# e-cig_controller.net
KiCad netlist of a schematic drawn in EAGLE
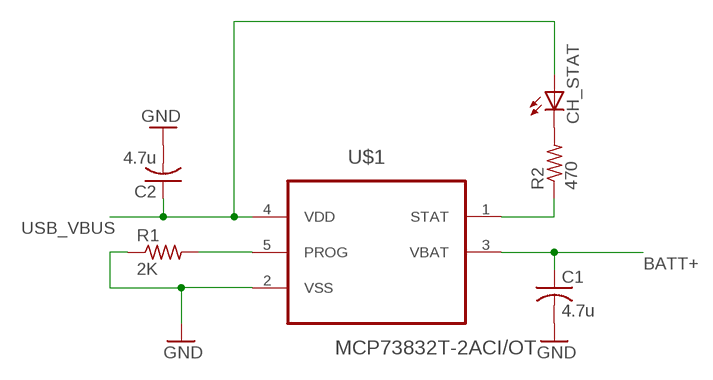
[diagram p0: schematic, sheet 1]
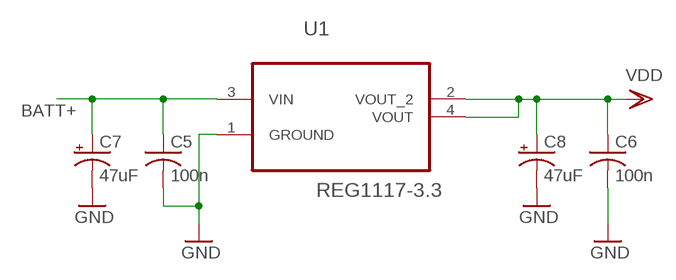
[diagram p1: schematic, sheet 2]
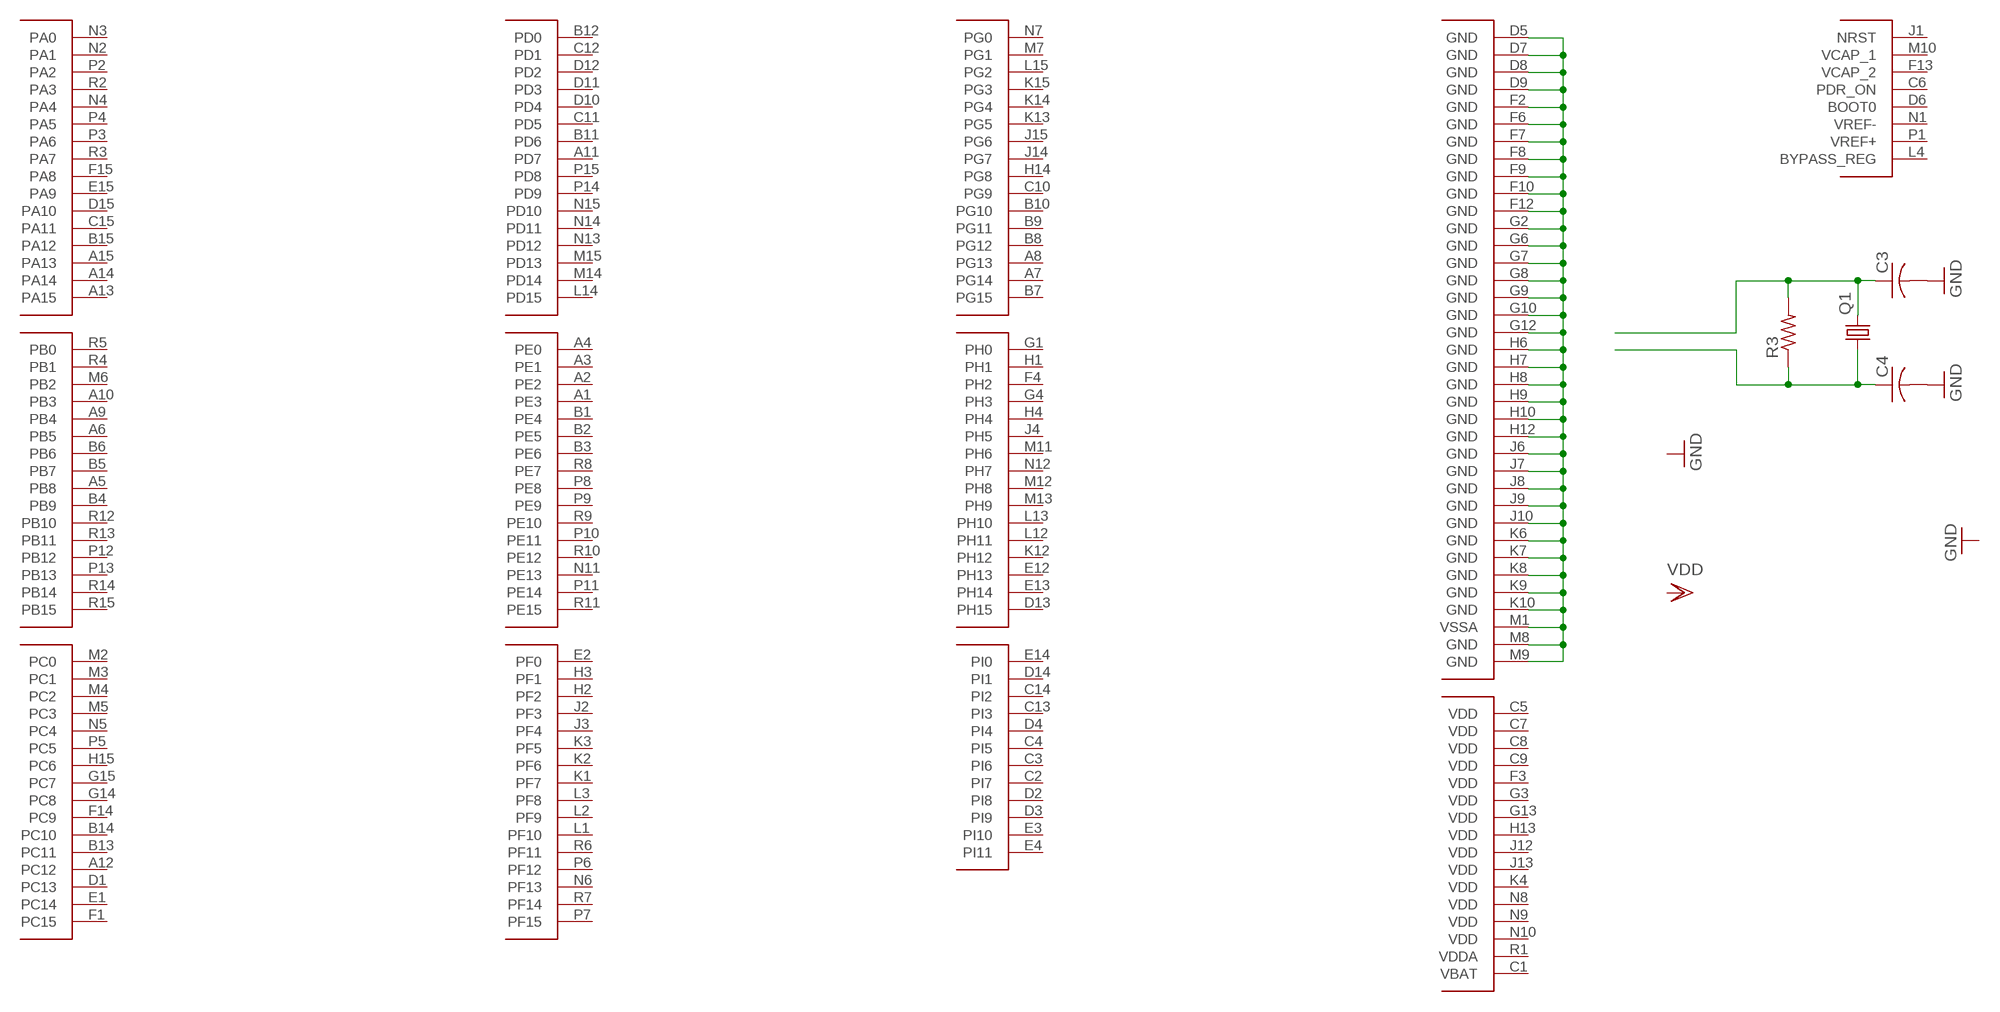
[diagram p2: schematic, sheet 3]

(export (version "E")
  (design (tool "Eeschema 10.0.6"))
  (components
    (comp (ref "C5")
      (value "100n")
      (footprint "eagle-import:C0603")
      (libsource (lib "eagle-import") (part "C-USC0603"))
    )
    (comp (ref "C6")
      (value "100n")
      (footprint "eagle-import:C0603")
      (libsource (lib "eagle-import") (part "C-USC0603"))
    )
    (comp (ref "C7")
      (value "47uF")
      (footprint "eagle-import:A_3216-18W")
      (libsource (lib "eagle-import") (part "CPOL-USA/3216-18W"))
    )
    (comp (ref "C8")
      (value "47uF")
      (footprint "eagle-import:A_3216-18W")
      (libsource (lib "eagle-import") (part "CPOL-USA/3216-18W"))
    )
    (comp (ref "U1")
      (value "REG1117-3.3")
      (footprint "eagle-import:SOT230P700X180-4N")
      (libsource (lib "eagle-import") (part "REG1117-3.3"))
    )
    (comp (ref "C1")
      (value "4.7u")
      (footprint "eagle-import:C0603")
      (libsource (lib "eagle-import") (part "C-USC0603"))
    )
    (comp (ref "C2")
      (value "4.7u")
      (footprint "eagle-import:C0603")
      (libsource (lib "eagle-import") (part "C-USC0603"))
    )
    (comp (ref "CH_STAT")
      (value "LEDCHIP-LED0603")
      (footprint "eagle-import:CHIP-LED0603")
      (libsource (lib "eagle-import") (part "LEDCHIP-LED0603"))
    )
    (comp (ref "R1")
      (value "2K")
      (footprint "eagle-import:R0603")
      (libsource (lib "eagle-import") (part "R-US_R0603"))
    )
    (comp (ref "R2")
      (value "470")
      (footprint "eagle-import:R0603")
      (libsource (lib "eagle-import") (part "R-US_R0603"))
    )
    (comp (ref "U$1")
      (value "MCP73832T-2ACI/OT")
      (footprint "eagle-import:SOT95P280X145-5N")
      (libsource (lib "eagle-import") (part "MCP73832T-2ACI/OT"))
    )
    (comp (ref "C3")
      (value "C-USC0603")
      (footprint "eagle-import:C0603")
      (libsource (lib "eagle-import") (part "C-USC0603"))
    )
    (comp (ref "C4")
      (value "C-USC0603")
      (footprint "eagle-import:C0603")
      (libsource (lib "eagle-import") (part "C-USC0603"))
    )
    (comp (ref "Q1")
      (value "CRYSTALHC49US")
      (footprint "eagle-import:HC49US")
      (libsource (lib "eagle-import") (part "CRYSTALHC49US"))
    )
    (comp (ref "R3")
      (value "R-US_R0603")
      (footprint "eagle-import:R0603")
      (libsource (lib "eagle-import") (part "R-US_R0603"))
    )
    (comp (ref "U$2")
      (value "STM32F407IG")
      (footprint "eagle-import:UFBGA176+25")
      (libsource (lib "eagle-import") (part "STM32F407IG"))
    )
  )
  (nets
    (net (code "1") (name "BATT+") (class "Default")
      (node (ref "C1") (pin "1") (pinfunction "1_1") (pintype "passive"))
      (node (ref "C5") (pin "1") (pinfunction "1_1") (pintype "passive"))
      (node (ref "C7") (pin "+") (pinfunction "+_+") (pintype "passive"))
      (node (ref "U$1") (pin "3") (pinfunction "VBAT_3") (pintype "output"))
      (node (ref "U1") (pin "3") (pinfunction "VIN_3") (pintype "input"))
    )
    (net (code "2") (name "GND") (class "Default")
      (node (ref "C1") (pin "2") (pinfunction "2_2") (pintype "passive"))
      (node (ref "C2") (pin "2") (pinfunction "2_2") (pintype "passive"))
      (node (ref "C3") (pin "2") (pinfunction "2_2") (pintype "passive"))
      (node (ref "C4") (pin "2") (pinfunction "2_2") (pintype "passive"))
      (node (ref "C5") (pin "2") (pinfunction "2_2") (pintype "passive"))
      (node (ref "C6") (pin "2") (pinfunction "2_2") (pintype "passive"))
      (node (ref "C7") (pin "-") (pinfunction "-_-") (pintype "passive"))
      (node (ref "C8") (pin "-") (pinfunction "-_-") (pintype "passive"))
      (node (ref "R1") (pin "1") (pinfunction "1_1") (pintype "passive"))
      (node (ref "U$1") (pin "2") (pinfunction "VSS_2") (pintype "power_in"))
      (node (ref "U1") (pin "1") (pinfunction "GROUND_1") (pintype "passive"))
    )
    (net (code "3") (name "Net-(C3-Pad1)") (class "Default")
      (node (ref "C3") (pin "1") (pinfunction "1_1") (pintype "passive"))
      (node (ref "Q1") (pin "2") (pinfunction "2_2") (pintype "passive"))
      (node (ref "R3") (pin "2") (pinfunction "2_2") (pintype "passive"))
    )
    (net (code "4") (name "Net-(C4-Pad1)") (class "Default")
      (node (ref "C4") (pin "1") (pinfunction "1_1") (pintype "passive"))
      (node (ref "Q1") (pin "1") (pinfunction "1_1") (pintype "passive"))
      (node (ref "R3") (pin "1") (pinfunction "1_1") (pintype "passive"))
    )
    (net (code "5") (name "Net-(CH_STAT-PadC)") (class "Default")
      (node (ref "CH_STAT") (pin "C") (pinfunction "C_C") (pintype "passive"))
      (node (ref "R2") (pin "2") (pinfunction "2_2") (pintype "passive"))
    )
    (net (code "6") (name "Net-(U$1-PROG)") (class "Default")
      (node (ref "R1") (pin "2") (pinfunction "2_2") (pintype "passive"))
      (node (ref "U$1") (pin "5") (pinfunction "PROG_5") (pintype "input"))
    )
    (net (code "7") (name "Net-(U$1-STAT)") (class "Default")
      (node (ref "R2") (pin "1") (pinfunction "1_1") (pintype "passive"))
      (node (ref "U$1") (pin "1") (pinfunction "STAT_1") (pintype "output"))
    )
    (net (code "8") (name "Net-(U$2-VSSA)") (class "Default")
      (node (ref "U$2") (pin "D5") (pinfunction "GND_D5") (pintype "bidirectional"))
      (node (ref "U$2") (pin "D7") (pinfunction "GND_D7") (pintype "bidirectional"))
      (node (ref "U$2") (pin "D8") (pinfunction "GND_D8") (pintype "bidirectional"))
      (node (ref "U$2") (pin "D9") (pinfunction "GND_D9") (pintype "bidirectional"))
      (node (ref "U$2") (pin "F10") (pinfunction "GND_F10") (pintype "bidirectional"))
      (node (ref "U$2") (pin "F12") (pinfunction "GND_F12") (pintype "bidirectional"))
      (node (ref "U$2") (pin "F2") (pinfunction "GND_F2") (pintype "bidirectional"))
      (node (ref "U$2") (pin "F6") (pinfunction "GND_F6") (pintype "bidirectional"))
      (node (ref "U$2") (pin "F7") (pinfunction "GND_F7") (pintype "bidirectional"))
      (node (ref "U$2") (pin "F8") (pinfunction "GND_F8") (pintype "bidirectional"))
      (node (ref "U$2") (pin "F9") (pinfunction "GND_F9") (pintype "bidirectional"))
      (node (ref "U$2") (pin "G10") (pinfunction "GND_G10") (pintype "bidirectional"))
      (node (ref "U$2") (pin "G12") (pinfunction "GND_G12") (pintype "bidirectional"))
      (node (ref "U$2") (pin "G2") (pinfunction "GND_G2") (pintype "bidirectional"))
      (node (ref "U$2") (pin "G6") (pinfunction "GND_G6") (pintype "bidirectional"))
      (node (ref "U$2") (pin "G7") (pinfunction "GND_G7") (pintype "bidirectional"))
      (node (ref "U$2") (pin "G8") (pinfunction "GND_G8") (pintype "bidirectional"))
      (node (ref "U$2") (pin "G9") (pinfunction "GND_G9") (pintype "bidirectional"))
      (node (ref "U$2") (pin "H10") (pinfunction "GND_H10") (pintype "bidirectional"))
      (node (ref "U$2") (pin "H12") (pinfunction "GND_H12") (pintype "bidirectional"))
      (node (ref "U$2") (pin "H6") (pinfunction "GND_H6") (pintype "bidirectional"))
      (node (ref "U$2") (pin "H7") (pinfunction "GND_H7") (pintype "bidirectional"))
      (node (ref "U$2") (pin "H8") (pinfunction "GND_H8") (pintype "bidirectional"))
      (node (ref "U$2") (pin "H9") (pinfunction "GND_H9") (pintype "bidirectional"))
      (node (ref "U$2") (pin "J10") (pinfunction "GND_J10") (pintype "bidirectional"))
      (node (ref "U$2") (pin "J6") (pinfunction "GND_J6") (pintype "bidirectional"))
      (node (ref "U$2") (pin "J7") (pinfunction "GND_J7") (pintype "bidirectional"))
      (node (ref "U$2") (pin "J8") (pinfunction "GND_J8") (pintype "bidirectional"))
      (node (ref "U$2") (pin "J9") (pinfunction "GND_J9") (pintype "bidirectional"))
      (node (ref "U$2") (pin "K10") (pinfunction "GND_K10") (pintype "bidirectional"))
      (node (ref "U$2") (pin "K6") (pinfunction "GND_K6") (pintype "bidirectional"))
      (node (ref "U$2") (pin "K7") (pinfunction "GND_K7") (pintype "bidirectional"))
      (node (ref "U$2") (pin "K8") (pinfunction "GND_K8") (pintype "bidirectional"))
      (node (ref "U$2") (pin "K9") (pinfunction "GND_K9") (pintype "bidirectional"))
      (node (ref "U$2") (pin "M1") (pinfunction "VSSA_M1") (pintype "bidirectional"))
      (node (ref "U$2") (pin "M8") (pinfunction "GND_M8") (pintype "bidirectional"))
      (node (ref "U$2") (pin "M9") (pinfunction "GND_M9") (pintype "bidirectional"))
    )
    (net (code "9") (name "USB_VBUS") (class "Default")
      (node (ref "C2") (pin "1") (pinfunction "1_1") (pintype "passive"))
      (node (ref "CH_STAT") (pin "A") (pinfunction "A_A") (pintype "passive"))
      (node (ref "U$1") (pin "4") (pinfunction "VDD_4") (pintype "power_in"))
    )
    (net (code "10") (name "VDD") (class "Default")
      (node (ref "C6") (pin "1") (pinfunction "1_1") (pintype "passive"))
      (node (ref "C8") (pin "+") (pinfunction "+_+") (pintype "passive"))
      (node (ref "U1") (pin "2") (pinfunction "VOUT_2_2") (pintype "output"))
      (node (ref "U1") (pin "4") (pinfunction "VOUT_4") (pintype "output"))
    )
    (net (code "11") (name "unconnected-(U$2-BOOT0-PadD6)") (class "Default")
      (node (ref "U$2") (pin "D6") (pinfunction "BOOT0_D6") (pintype "bidirectional"))
    )
    (net (code "12") (name "unconnected-(U$2-BYPASS_REG-PadL4)") (class "Default")
      (node (ref "U$2") (pin "L4") (pinfunction "BYPASS_REG_L4") (pintype "bidirectional"))
    )
    (net (code "13") (name "unconnected-(U$2-NRST-PadJ1)") (class "Default")
      (node (ref "U$2") (pin "J1") (pinfunction "NRST_J1") (pintype "bidirectional"))
    )
    (net (code "14") (name "unconnected-(U$2-PA0-PadN3)") (class "Default")
      (node (ref "U$2") (pin "N3") (pinfunction "PA0_N3") (pintype "bidirectional"))
    )
    (net (code "15") (name "unconnected-(U$2-PA1-PadN2)") (class "Default")
      (node (ref "U$2") (pin "N2") (pinfunction "PA1_N2") (pintype "bidirectional"))
    )
    (net (code "16") (name "unconnected-(U$2-PA2-PadP2)") (class "Default")
      (node (ref "U$2") (pin "P2") (pinfunction "PA2_P2") (pintype "bidirectional"))
    )
    (net (code "17") (name "unconnected-(U$2-PA3-PadR2)") (class "Default")
      (node (ref "U$2") (pin "R2") (pinfunction "PA3_R2") (pintype "bidirectional"))
    )
    (net (code "18") (name "unconnected-(U$2-PA4-PadN4)") (class "Default")
      (node (ref "U$2") (pin "N4") (pinfunction "PA4_N4") (pintype "bidirectional"))
    )
    (net (code "19") (name "unconnected-(U$2-PA5-PadP4)") (class "Default")
      (node (ref "U$2") (pin "P4") (pinfunction "PA5_P4") (pintype "bidirectional"))
    )
    (net (code "20") (name "unconnected-(U$2-PA6-PadP3)") (class "Default")
      (node (ref "U$2") (pin "P3") (pinfunction "PA6_P3") (pintype "bidirectional"))
    )
    (net (code "21") (name "unconnected-(U$2-PA7-PadR3)") (class "Default")
      (node (ref "U$2") (pin "R3") (pinfunction "PA7_R3") (pintype "bidirectional"))
    )
    (net (code "22") (name "unconnected-(U$2-PA8-PadF15)") (class "Default")
      (node (ref "U$2") (pin "F15") (pinfunction "PA8_F15") (pintype "bidirectional"))
    )
    (net (code "23") (name "unconnected-(U$2-PA9-PadE15)") (class "Default")
      (node (ref "U$2") (pin "E15") (pinfunction "PA9_E15") (pintype "bidirectional"))
    )
    (net (code "24") (name "unconnected-(U$2-PA10-PadD15)") (class "Default")
      (node (ref "U$2") (pin "D15") (pinfunction "PA10_D15") (pintype "bidirectional"))
    )
    (net (code "25") (name "unconnected-(U$2-PA11-PadC15)") (class "Default")
      (node (ref "U$2") (pin "C15") (pinfunction "PA11_C15") (pintype "bidirectional"))
    )
    (net (code "26") (name "unconnected-(U$2-PA12-PadB15)") (class "Default")
      (node (ref "U$2") (pin "B15") (pinfunction "PA12_B15") (pintype "bidirectional"))
    )
    (net (code "27") (name "unconnected-(U$2-PA13-PadA15)") (class "Default")
      (node (ref "U$2") (pin "A15") (pinfunction "PA13_A15") (pintype "bidirectional"))
    )
    (net (code "28") (name "unconnected-(U$2-PA14-PadA14)") (class "Default")
      (node (ref "U$2") (pin "A14") (pinfunction "PA14_A14") (pintype "bidirectional"))
    )
    (net (code "29") (name "unconnected-(U$2-PA15-PadA13)") (class "Default")
      (node (ref "U$2") (pin "A13") (pinfunction "PA15_A13") (pintype "bidirectional"))
    )
    (net (code "30") (name "unconnected-(U$2-PB0-PadR5)") (class "Default")
      (node (ref "U$2") (pin "R5") (pinfunction "PB0_R5") (pintype "bidirectional"))
    )
    (net (code "31") (name "unconnected-(U$2-PB1-PadR4)") (class "Default")
      (node (ref "U$2") (pin "R4") (pinfunction "PB1_R4") (pintype "bidirectional"))
    )
    (net (code "32") (name "unconnected-(U$2-PB2-PadM6)") (class "Default")
      (node (ref "U$2") (pin "M6") (pinfunction "PB2_M6") (pintype "bidirectional"))
    )
    (net (code "33") (name "unconnected-(U$2-PB3-PadA10)") (class "Default")
      (node (ref "U$2") (pin "A10") (pinfunction "PB3_A10") (pintype "bidirectional"))
    )
    (net (code "34") (name "unconnected-(U$2-PB4-PadA9)") (class "Default")
      (node (ref "U$2") (pin "A9") (pinfunction "PB4_A9") (pintype "bidirectional"))
    )
    (net (code "35") (name "unconnected-(U$2-PB5-PadA6)") (class "Default")
      (node (ref "U$2") (pin "A6") (pinfunction "PB5_A6") (pintype "bidirectional"))
    )
    (net (code "36") (name "unconnected-(U$2-PB6-PadB6)") (class "Default")
      (node (ref "U$2") (pin "B6") (pinfunction "PB6_B6") (pintype "bidirectional"))
    )
    (net (code "37") (name "unconnected-(U$2-PB7-PadB5)") (class "Default")
      (node (ref "U$2") (pin "B5") (pinfunction "PB7_B5") (pintype "bidirectional"))
    )
    (net (code "38") (name "unconnected-(U$2-PB8-PadA5)") (class "Default")
      (node (ref "U$2") (pin "A5") (pinfunction "PB8_A5") (pintype "bidirectional"))
    )
    (net (code "39") (name "unconnected-(U$2-PB9-PadB4)") (class "Default")
      (node (ref "U$2") (pin "B4") (pinfunction "PB9_B4") (pintype "bidirectional"))
    )
    (net (code "40") (name "unconnected-(U$2-PB10-PadR12)") (class "Default")
      (node (ref "U$2") (pin "R12") (pinfunction "PB10_R12") (pintype "bidirectional"))
    )
    (net (code "41") (name "unconnected-(U$2-PB11-PadR13)") (class "Default")
      (node (ref "U$2") (pin "R13") (pinfunction "PB11_R13") (pintype "bidirectional"))
    )
    (net (code "42") (name "unconnected-(U$2-PB12-PadP12)") (class "Default")
      (node (ref "U$2") (pin "P12") (pinfunction "PB12_P12") (pintype "bidirectional"))
    )
    (net (code "43") (name "unconnected-(U$2-PB13-PadP13)") (class "Default")
      (node (ref "U$2") (pin "P13") (pinfunction "PB13_P13") (pintype "bidirectional"))
    )
    (net (code "44") (name "unconnected-(U$2-PB14-PadR14)") (class "Default")
      (node (ref "U$2") (pin "R14") (pinfunction "PB14_R14") (pintype "bidirectional"))
    )
    (net (code "45") (name "unconnected-(U$2-PB15-PadR15)") (class "Default")
      (node (ref "U$2") (pin "R15") (pinfunction "PB15_R15") (pintype "bidirectional"))
    )
    (net (code "46") (name "unconnected-(U$2-PC0-PadM2)") (class "Default")
      (node (ref "U$2") (pin "M2") (pinfunction "PC0_M2") (pintype "bidirectional"))
    )
    (net (code "47") (name "unconnected-(U$2-PC1-PadM3)") (class "Default")
      (node (ref "U$2") (pin "M3") (pinfunction "PC1_M3") (pintype "bidirectional"))
    )
    (net (code "48") (name "unconnected-(U$2-PC2-PadM4)") (class "Default")
      (node (ref "U$2") (pin "M4") (pinfunction "PC2_M4") (pintype "bidirectional"))
    )
    (net (code "49") (name "unconnected-(U$2-PC3-PadM5)") (class "Default")
      (node (ref "U$2") (pin "M5") (pinfunction "PC3_M5") (pintype "bidirectional"))
    )
    (net (code "50") (name "unconnected-(U$2-PC4-PadN5)") (class "Default")
      (node (ref "U$2") (pin "N5") (pinfunction "PC4_N5") (pintype "bidirectional"))
    )
    (net (code "51") (name "unconnected-(U$2-PC5-PadP5)") (class "Default")
      (node (ref "U$2") (pin "P5") (pinfunction "PC5_P5") (pintype "bidirectional"))
    )
    (net (code "52") (name "unconnected-(U$2-PC6-PadH15)") (class "Default")
      (node (ref "U$2") (pin "H15") (pinfunction "PC6_H15") (pintype "bidirectional"))
    )
    (net (code "53") (name "unconnected-(U$2-PC7-PadG15)") (class "Default")
      (node (ref "U$2") (pin "G15") (pinfunction "PC7_G15") (pintype "bidirectional"))
    )
    (net (code "54") (name "unconnected-(U$2-PC8-PadG14)") (class "Default")
      (node (ref "U$2") (pin "G14") (pinfunction "PC8_G14") (pintype "bidirectional"))
    )
    (net (code "55") (name "unconnected-(U$2-PC9-PadF14)") (class "Default")
      (node (ref "U$2") (pin "F14") (pinfunction "PC9_F14") (pintype "bidirectional"))
    )
    (net (code "56") (name "unconnected-(U$2-PC10-PadB14)") (class "Default")
      (node (ref "U$2") (pin "B14") (pinfunction "PC10_B14") (pintype "bidirectional"))
    )
    (net (code "57") (name "unconnected-(U$2-PC11-PadB13)") (class "Default")
      (node (ref "U$2") (pin "B13") (pinfunction "PC11_B13") (pintype "bidirectional"))
    )
    (net (code "58") (name "unconnected-(U$2-PC12-PadA12)") (class "Default")
      (node (ref "U$2") (pin "A12") (pinfunction "PC12_A12") (pintype "bidirectional"))
    )
    (net (code "59") (name "unconnected-(U$2-PC13-PadD1)") (class "Default")
      (node (ref "U$2") (pin "D1") (pinfunction "PC13_D1") (pintype "bidirectional"))
    )
    (net (code "60") (name "unconnected-(U$2-PC14-PadE1)") (class "Default")
      (node (ref "U$2") (pin "E1") (pinfunction "PC14_E1") (pintype "bidirectional"))
    )
    (net (code "61") (name "unconnected-(U$2-PC15-PadF1)") (class "Default")
      (node (ref "U$2") (pin "F1") (pinfunction "PC15_F1") (pintype "bidirectional"))
    )
    (net (code "62") (name "unconnected-(U$2-PD0-PadB12)") (class "Default")
      (node (ref "U$2") (pin "B12") (pinfunction "PD0_B12") (pintype "bidirectional"))
    )
    (net (code "63") (name "unconnected-(U$2-PD1-PadC12)") (class "Default")
      (node (ref "U$2") (pin "C12") (pinfunction "PD1_C12") (pintype "bidirectional"))
    )
    (net (code "64") (name "unconnected-(U$2-PD2-PadD12)") (class "Default")
      (node (ref "U$2") (pin "D12") (pinfunction "PD2_D12") (pintype "bidirectional"))
    )
    (net (code "65") (name "unconnected-(U$2-PD3-PadD11)") (class "Default")
      (node (ref "U$2") (pin "D11") (pinfunction "PD3_D11") (pintype "bidirectional"))
    )
    (net (code "66") (name "unconnected-(U$2-PD4-PadD10)") (class "Default")
      (node (ref "U$2") (pin "D10") (pinfunction "PD4_D10") (pintype "bidirectional"))
    )
    (net (code "67") (name "unconnected-(U$2-PD5-PadC11)") (class "Default")
      (node (ref "U$2") (pin "C11") (pinfunction "PD5_C11") (pintype "bidirectional"))
    )
    (net (code "68") (name "unconnected-(U$2-PD6-PadB11)") (class "Default")
      (node (ref "U$2") (pin "B11") (pinfunction "PD6_B11") (pintype "bidirectional"))
    )
    (net (code "69") (name "unconnected-(U$2-PD7-PadA11)") (class "Default")
      (node (ref "U$2") (pin "A11") (pinfunction "PD7_A11") (pintype "bidirectional"))
    )
    (net (code "70") (name "unconnected-(U$2-PD8-PadP15)") (class "Default")
      (node (ref "U$2") (pin "P15") (pinfunction "PD8_P15") (pintype "bidirectional"))
    )
    (net (code "71") (name "unconnected-(U$2-PD9-PadP14)") (class "Default")
      (node (ref "U$2") (pin "P14") (pinfunction "PD9_P14") (pintype "bidirectional"))
    )
    (net (code "72") (name "unconnected-(U$2-PD10-PadN15)") (class "Default")
      (node (ref "U$2") (pin "N15") (pinfunction "PD10_N15") (pintype "bidirectional"))
    )
    (net (code "73") (name "unconnected-(U$2-PD11-PadN14)") (class "Default")
      (node (ref "U$2") (pin "N14") (pinfunction "PD11_N14") (pintype "bidirectional"))
    )
    (net (code "74") (name "unconnected-(U$2-PD12-PadN13)") (class "Default")
      (node (ref "U$2") (pin "N13") (pinfunction "PD12_N13") (pintype "bidirectional"))
    )
    (net (code "75") (name "unconnected-(U$2-PD13-PadM15)") (class "Default")
      (node (ref "U$2") (pin "M15") (pinfunction "PD13_M15") (pintype "bidirectional"))
    )
    (net (code "76") (name "unconnected-(U$2-PD14-PadM14)") (class "Default")
      (node (ref "U$2") (pin "M14") (pinfunction "PD14_M14") (pintype "bidirectional"))
    )
    (net (code "77") (name "unconnected-(U$2-PD15-PadL14)") (class "Default")
      (node (ref "U$2") (pin "L14") (pinfunction "PD15_L14") (pintype "bidirectional"))
    )
    (net (code "78") (name "unconnected-(U$2-PDR_ON-PadC6)") (class "Default")
      (node (ref "U$2") (pin "C6") (pinfunction "PDR_ON_C6") (pintype "bidirectional"))
    )
    (net (code "79") (name "unconnected-(U$2-PE0-PadA4)") (class "Default")
      (node (ref "U$2") (pin "A4") (pinfunction "PE0_A4") (pintype "bidirectional"))
    )
    (net (code "80") (name "unconnected-(U$2-PE1-PadA3)") (class "Default")
      (node (ref "U$2") (pin "A3") (pinfunction "PE1_A3") (pintype "bidirectional"))
    )
    (net (code "81") (name "unconnected-(U$2-PE2-PadA2)") (class "Default")
      (node (ref "U$2") (pin "A2") (pinfunction "PE2_A2") (pintype "bidirectional"))
    )
    (net (code "82") (name "unconnected-(U$2-PE3-PadA1)") (class "Default")
      (node (ref "U$2") (pin "A1") (pinfunction "PE3_A1") (pintype "bidirectional"))
    )
    (net (code "83") (name "unconnected-(U$2-PE4-PadB1)") (class "Default")
      (node (ref "U$2") (pin "B1") (pinfunction "PE4_B1") (pintype "bidirectional"))
    )
    (net (code "84") (name "unconnected-(U$2-PE5-PadB2)") (class "Default")
      (node (ref "U$2") (pin "B2") (pinfunction "PE5_B2") (pintype "bidirectional"))
    )
    (net (code "85") (name "unconnected-(U$2-PE6-PadB3)") (class "Default")
      (node (ref "U$2") (pin "B3") (pinfunction "PE6_B3") (pintype "bidirectional"))
    )
    (net (code "86") (name "unconnected-(U$2-PE7-PadR8)") (class "Default")
      (node (ref "U$2") (pin "R8") (pinfunction "PE7_R8") (pintype "bidirectional"))
    )
    (net (code "87") (name "unconnected-(U$2-PE8-PadP8)") (class "Default")
      (node (ref "U$2") (pin "P8") (pinfunction "PE8_P8") (pintype "bidirectional"))
    )
    (net (code "88") (name "unconnected-(U$2-PE9-PadP9)") (class "Default")
      (node (ref "U$2") (pin "P9") (pinfunction "PE9_P9") (pintype "bidirectional"))
    )
    (net (code "89") (name "unconnected-(U$2-PE10-PadR9)") (class "Default")
      (node (ref "U$2") (pin "R9") (pinfunction "PE10_R9") (pintype "bidirectional"))
    )
    (net (code "90") (name "unconnected-(U$2-PE11-PadP10)") (class "Default")
      (node (ref "U$2") (pin "P10") (pinfunction "PE11_P10") (pintype "bidirectional"))
    )
    (net (code "91") (name "unconnected-(U$2-PE12-PadR10)") (class "Default")
      (node (ref "U$2") (pin "R10") (pinfunction "PE12_R10") (pintype "bidirectional"))
    )
    (net (code "92") (name "unconnected-(U$2-PE13-PadN11)") (class "Default")
      (node (ref "U$2") (pin "N11") (pinfunction "PE13_N11") (pintype "bidirectional"))
    )
    (net (code "93") (name "unconnected-(U$2-PE14-PadP11)") (class "Default")
      (node (ref "U$2") (pin "P11") (pinfunction "PE14_P11") (pintype "bidirectional"))
    )
    (net (code "94") (name "unconnected-(U$2-PE15-PadR11)") (class "Default")
      (node (ref "U$2") (pin "R11") (pinfunction "PE15_R11") (pintype "bidirectional"))
    )
    (net (code "95") (name "unconnected-(U$2-PF0-PadE2)") (class "Default")
      (node (ref "U$2") (pin "E2") (pinfunction "PF0_E2") (pintype "bidirectional"))
    )
    (net (code "96") (name "unconnected-(U$2-PF1-PadH3)") (class "Default")
      (node (ref "U$2") (pin "H3") (pinfunction "PF1_H3") (pintype "bidirectional"))
    )
    (net (code "97") (name "unconnected-(U$2-PF2-PadH2)") (class "Default")
      (node (ref "U$2") (pin "H2") (pinfunction "PF2_H2") (pintype "bidirectional"))
    )
    (net (code "98") (name "unconnected-(U$2-PF3-PadJ2)") (class "Default")
      (node (ref "U$2") (pin "J2") (pinfunction "PF3_J2") (pintype "bidirectional"))
    )
    (net (code "99") (name "unconnected-(U$2-PF4-PadJ3)") (class "Default")
      (node (ref "U$2") (pin "J3") (pinfunction "PF4_J3") (pintype "bidirectional"))
    )
    (net (code "100") (name "unconnected-(U$2-PF5-PadK3)") (class "Default")
      (node (ref "U$2") (pin "K3") (pinfunction "PF5_K3") (pintype "bidirectional"))
    )
    (net (code "101") (name "unconnected-(U$2-PF6-PadK2)") (class "Default")
      (node (ref "U$2") (pin "K2") (pinfunction "PF6_K2") (pintype "bidirectional"))
    )
    (net (code "102") (name "unconnected-(U$2-PF7-PadK1)") (class "Default")
      (node (ref "U$2") (pin "K1") (pinfunction "PF7_K1") (pintype "bidirectional"))
    )
    (net (code "103") (name "unconnected-(U$2-PF8-PadL3)") (class "Default")
      (node (ref "U$2") (pin "L3") (pinfunction "PF8_L3") (pintype "bidirectional"))
    )
    (net (code "104") (name "unconnected-(U$2-PF9-PadL2)") (class "Default")
      (node (ref "U$2") (pin "L2") (pinfunction "PF9_L2") (pintype "bidirectional"))
    )
    (net (code "105") (name "unconnected-(U$2-PF10-PadL1)") (class "Default")
      (node (ref "U$2") (pin "L1") (pinfunction "PF10_L1") (pintype "bidirectional"))
    )
    (net (code "106") (name "unconnected-(U$2-PF11-PadR6)") (class "Default")
      (node (ref "U$2") (pin "R6") (pinfunction "PF11_R6") (pintype "bidirectional"))
    )
    (net (code "107") (name "unconnected-(U$2-PF12-PadP6)") (class "Default")
      (node (ref "U$2") (pin "P6") (pinfunction "PF12_P6") (pintype "bidirectional"))
    )
    (net (code "108") (name "unconnected-(U$2-PF13-PadN6)") (class "Default")
      (node (ref "U$2") (pin "N6") (pinfunction "PF13_N6") (pintype "bidirectional"))
    )
    (net (code "109") (name "unconnected-(U$2-PF14-PadR7)") (class "Default")
      (node (ref "U$2") (pin "R7") (pinfunction "PF14_R7") (pintype "bidirectional"))
    )
    (net (code "110") (name "unconnected-(U$2-PF15-PadP7)") (class "Default")
      (node (ref "U$2") (pin "P7") (pinfunction "PF15_P7") (pintype "bidirectional"))
    )
    (net (code "111") (name "unconnected-(U$2-PG0-PadN7)") (class "Default")
      (node (ref "U$2") (pin "N7") (pinfunction "PG0_N7") (pintype "bidirectional"))
    )
    (net (code "112") (name "unconnected-(U$2-PG1-PadM7)") (class "Default")
      (node (ref "U$2") (pin "M7") (pinfunction "PG1_M7") (pintype "bidirectional"))
    )
    (net (code "113") (name "unconnected-(U$2-PG2-PadL15)") (class "Default")
      (node (ref "U$2") (pin "L15") (pinfunction "PG2_L15") (pintype "bidirectional"))
    )
    (net (code "114") (name "unconnected-(U$2-PG3-PadK15)") (class "Default")
      (node (ref "U$2") (pin "K15") (pinfunction "PG3_K15") (pintype "bidirectional"))
    )
    (net (code "115") (name "unconnected-(U$2-PG4-PadK14)") (class "Default")
      (node (ref "U$2") (pin "K14") (pinfunction "PG4_K14") (pintype "bidirectional"))
    )
    (net (code "116") (name "unconnected-(U$2-PG5-PadK13)") (class "Default")
      (node (ref "U$2") (pin "K13") (pinfunction "PG5_K13") (pintype "bidirectional"))
    )
    (net (code "117") (name "unconnected-(U$2-PG6-PadJ15)") (class "Default")
      (node (ref "U$2") (pin "J15") (pinfunction "PG6_J15") (pintype "bidirectional"))
    )
    (net (code "118") (name "unconnected-(U$2-PG7-PadJ14)") (class "Default")
      (node (ref "U$2") (pin "J14") (pinfunction "PG7_J14") (pintype "bidirectional"))
    )
    (net (code "119") (name "unconnected-(U$2-PG8-PadH14)") (class "Default")
      (node (ref "U$2") (pin "H14") (pinfunction "PG8_H14") (pintype "bidirectional"))
    )
    (net (code "120") (name "unconnected-(U$2-PG9-PadC10)") (class "Default")
      (node (ref "U$2") (pin "C10") (pinfunction "PG9_C10") (pintype "bidirectional"))
    )
    (net (code "121") (name "unconnected-(U$2-PG10-PadB10)") (class "Default")
      (node (ref "U$2") (pin "B10") (pinfunction "PG10_B10") (pintype "bidirectional"))
    )
    (net (code "122") (name "unconnected-(U$2-PG11-PadB9)") (class "Default")
      (node (ref "U$2") (pin "B9") (pinfunction "PG11_B9") (pintype "bidirectional"))
    )
    (net (code "123") (name "unconnected-(U$2-PG12-PadB8)") (class "Default")
      (node (ref "U$2") (pin "B8") (pinfunction "PG12_B8") (pintype "bidirectional"))
    )
    (net (code "124") (name "unconnected-(U$2-PG13-PadA8)") (class "Default")
      (node (ref "U$2") (pin "A8") (pinfunction "PG13_A8") (pintype "bidirectional"))
    )
    (net (code "125") (name "unconnected-(U$2-PG14-PadA7)") (class "Default")
      (node (ref "U$2") (pin "A7") (pinfunction "PG14_A7") (pintype "bidirectional"))
    )
    (net (code "126") (name "unconnected-(U$2-PG15-PadB7)") (class "Default")
      (node (ref "U$2") (pin "B7") (pinfunction "PG15_B7") (pintype "bidirectional"))
    )
    (net (code "127") (name "unconnected-(U$2-PH0-PadG1)") (class "Default")
      (node (ref "U$2") (pin "G1") (pinfunction "PH0_G1") (pintype "bidirectional"))
    )
    (net (code "128") (name "unconnected-(U$2-PH1-PadH1)") (class "Default")
      (node (ref "U$2") (pin "H1") (pinfunction "PH1_H1") (pintype "bidirectional"))
    )
    (net (code "129") (name "unconnected-(U$2-PH2-PadF4)") (class "Default")
      (node (ref "U$2") (pin "F4") (pinfunction "PH2_F4") (pintype "bidirectional"))
    )
    (net (code "130") (name "unconnected-(U$2-PH3-PadG4)") (class "Default")
      (node (ref "U$2") (pin "G4") (pinfunction "PH3_G4") (pintype "bidirectional"))
    )
    (net (code "131") (name "unconnected-(U$2-PH4-PadH4)") (class "Default")
      (node (ref "U$2") (pin "H4") (pinfunction "PH4_H4") (pintype "bidirectional"))
    )
    (net (code "132") (name "unconnected-(U$2-PH5-PadJ4)") (class "Default")
      (node (ref "U$2") (pin "J4") (pinfunction "PH5_J4") (pintype "bidirectional"))
    )
    (net (code "133") (name "unconnected-(U$2-PH6-PadM11)") (class "Default")
      (node (ref "U$2") (pin "M11") (pinfunction "PH6_M11") (pintype "bidirectional"))
    )
    (net (code "134") (name "unconnected-(U$2-PH7-PadN12)") (class "Default")
      (node (ref "U$2") (pin "N12") (pinfunction "PH7_N12") (pintype "bidirectional"))
    )
    (net (code "135") (name "unconnected-(U$2-PH8-PadM12)") (class "Default")
      (node (ref "U$2") (pin "M12") (pinfunction "PH8_M12") (pintype "bidirectional"))
    )
    (net (code "136") (name "unconnected-(U$2-PH9-PadM13)") (class "Default")
      (node (ref "U$2") (pin "M13") (pinfunction "PH9_M13") (pintype "bidirectional"))
    )
    (net (code "137") (name "unconnected-(U$2-PH10-PadL13)") (class "Default")
      (node (ref "U$2") (pin "L13") (pinfunction "PH10_L13") (pintype "bidirectional"))
    )
    (net (code "138") (name "unconnected-(U$2-PH11-PadL12)") (class "Default")
      (node (ref "U$2") (pin "L12") (pinfunction "PH11_L12") (pintype "bidirectional"))
    )
    (net (code "139") (name "unconnected-(U$2-PH12-PadK12)") (class "Default")
      (node (ref "U$2") (pin "K12") (pinfunction "PH12_K12") (pintype "bidirectional"))
    )
    (net (code "140") (name "unconnected-(U$2-PH13-PadE12)") (class "Default")
      (node (ref "U$2") (pin "E12") (pinfunction "PH13_E12") (pintype "bidirectional"))
    )
    (net (code "141") (name "unconnected-(U$2-PH14-PadE13)") (class "Default")
      (node (ref "U$2") (pin "E13") (pinfunction "PH14_E13") (pintype "bidirectional"))
    )
    (net (code "142") (name "unconnected-(U$2-PH15-PadD13)") (class "Default")
      (node (ref "U$2") (pin "D13") (pinfunction "PH15_D13") (pintype "bidirectional"))
    )
    (net (code "143") (name "unconnected-(U$2-PI0-PadE14)") (class "Default")
      (node (ref "U$2") (pin "E14") (pinfunction "PI0_E14") (pintype "bidirectional"))
    )
    (net (code "144") (name "unconnected-(U$2-PI1-PadD14)") (class "Default")
      (node (ref "U$2") (pin "D14") (pinfunction "PI1_D14") (pintype "bidirectional"))
    )
    (net (code "145") (name "unconnected-(U$2-PI2-PadC14)") (class "Default")
      (node (ref "U$2") (pin "C14") (pinfunction "PI2_C14") (pintype "bidirectional"))
    )
    (net (code "146") (name "unconnected-(U$2-PI3-PadC13)") (class "Default")
      (node (ref "U$2") (pin "C13") (pinfunction "PI3_C13") (pintype "bidirectional"))
    )
    (net (code "147") (name "unconnected-(U$2-PI4-PadD4)") (class "Default")
      (node (ref "U$2") (pin "D4") (pinfunction "PI4_D4") (pintype "bidirectional"))
    )
    (net (code "148") (name "unconnected-(U$2-PI5-PadC4)") (class "Default")
      (node (ref "U$2") (pin "C4") (pinfunction "PI5_C4") (pintype "bidirectional"))
    )
    (net (code "149") (name "unconnected-(U$2-PI6-PadC3)") (class "Default")
      (node (ref "U$2") (pin "C3") (pinfunction "PI6_C3") (pintype "bidirectional"))
    )
    (net (code "150") (name "unconnected-(U$2-PI7-PadC2)") (class "Default")
      (node (ref "U$2") (pin "C2") (pinfunction "PI7_C2") (pintype "bidirectional"))
    )
    (net (code "151") (name "unconnected-(U$2-PI8-PadD2)") (class "Default")
      (node (ref "U$2") (pin "D2") (pinfunction "PI8_D2") (pintype "bidirectional"))
    )
    (net (code "152") (name "unconnected-(U$2-PI9-PadD3)") (class "Default")
      (node (ref "U$2") (pin "D3") (pinfunction "PI9_D3") (pintype "bidirectional"))
    )
    (net (code "153") (name "unconnected-(U$2-PI10-PadE3)") (class "Default")
      (node (ref "U$2") (pin "E3") (pinfunction "PI10_E3") (pintype "bidirectional"))
    )
    (net (code "154") (name "unconnected-(U$2-PI11-PadE4)") (class "Default")
      (node (ref "U$2") (pin "E4") (pinfunction "PI11_E4") (pintype "bidirectional"))
    )
    (net (code "155") (name "unconnected-(U$2-VBAT-PadC1)") (class "Default")
      (node (ref "U$2") (pin "C1") (pinfunction "VBAT_C1") (pintype "bidirectional"))
    )
    (net (code "156") (name "unconnected-(U$2-VCAP_1-PadM10)") (class "Default")
      (node (ref "U$2") (pin "M10") (pinfunction "VCAP_1_M10") (pintype "bidirectional"))
    )
    (net (code "157") (name "unconnected-(U$2-VCAP_2-PadF13)") (class "Default")
      (node (ref "U$2") (pin "F13") (pinfunction "VCAP_2_F13") (pintype "bidirectional"))
    )
    (net (code "158") (name "unconnected-(U$2-VDD-PadC5)") (class "Default")
      (node (ref "U$2") (pin "C5") (pinfunction "VDD_C5") (pintype "bidirectional"))
    )
    (net (code "159") (name "unconnected-(U$2-VDD-PadC7)") (class "Default")
      (node (ref "U$2") (pin "C7") (pinfunction "VDD_C7") (pintype "bidirectional"))
    )
    (net (code "160") (name "unconnected-(U$2-VDD-PadC8)") (class "Default")
      (node (ref "U$2") (pin "C8") (pinfunction "VDD_C8") (pintype "bidirectional"))
    )
    (net (code "161") (name "unconnected-(U$2-VDD-PadC9)") (class "Default")
      (node (ref "U$2") (pin "C9") (pinfunction "VDD_C9") (pintype "bidirectional"))
    )
    (net (code "162") (name "unconnected-(U$2-VDD-PadF3)") (class "Default")
      (node (ref "U$2") (pin "F3") (pinfunction "VDD_F3") (pintype "bidirectional"))
    )
    (net (code "163") (name "unconnected-(U$2-VDD-PadG3)") (class "Default")
      (node (ref "U$2") (pin "G3") (pinfunction "VDD_G3") (pintype "bidirectional"))
    )
    (net (code "164") (name "unconnected-(U$2-VDD-PadG13)") (class "Default")
      (node (ref "U$2") (pin "G13") (pinfunction "VDD_G13") (pintype "bidirectional"))
    )
    (net (code "165") (name "unconnected-(U$2-VDD-PadH13)") (class "Default")
      (node (ref "U$2") (pin "H13") (pinfunction "VDD_H13") (pintype "bidirectional"))
    )
    (net (code "166") (name "unconnected-(U$2-VDD-PadJ12)") (class "Default")
      (node (ref "U$2") (pin "J12") (pinfunction "VDD_J12") (pintype "bidirectional"))
    )
    (net (code "167") (name "unconnected-(U$2-VDD-PadJ13)") (class "Default")
      (node (ref "U$2") (pin "J13") (pinfunction "VDD_J13") (pintype "bidirectional"))
    )
    (net (code "168") (name "unconnected-(U$2-VDD-PadK4)") (class "Default")
      (node (ref "U$2") (pin "K4") (pinfunction "VDD_K4") (pintype "bidirectional"))
    )
    (net (code "169") (name "unconnected-(U$2-VDD-PadN8)") (class "Default")
      (node (ref "U$2") (pin "N8") (pinfunction "VDD_N8") (pintype "bidirectional"))
    )
    (net (code "170") (name "unconnected-(U$2-VDD-PadN9)") (class "Default")
      (node (ref "U$2") (pin "N9") (pinfunction "VDD_N9") (pintype "bidirectional"))
    )
    (net (code "171") (name "unconnected-(U$2-VDD-PadN10)") (class "Default")
      (node (ref "U$2") (pin "N10") (pinfunction "VDD_N10") (pintype "bidirectional"))
    )
    (net (code "172") (name "unconnected-(U$2-VDDA-PadR1)") (class "Default")
      (node (ref "U$2") (pin "R1") (pinfunction "VDDA_R1") (pintype "bidirectional"))
    )
    (net (code "173") (name "unconnected-(U$2-VREF+-PadP1)") (class "Default")
      (node (ref "U$2") (pin "P1") (pinfunction "VREF+_P1") (pintype "bidirectional"))
    )
    (net (code "174") (name "unconnected-(U$2-VREF--PadN1)") (class "Default")
      (node (ref "U$2") (pin "N1") (pinfunction "VREF-_N1") (pintype "bidirectional"))
    )
  )
)
